# BEEP.net
KiCad netlist of a schematic drawn in Altium Designer
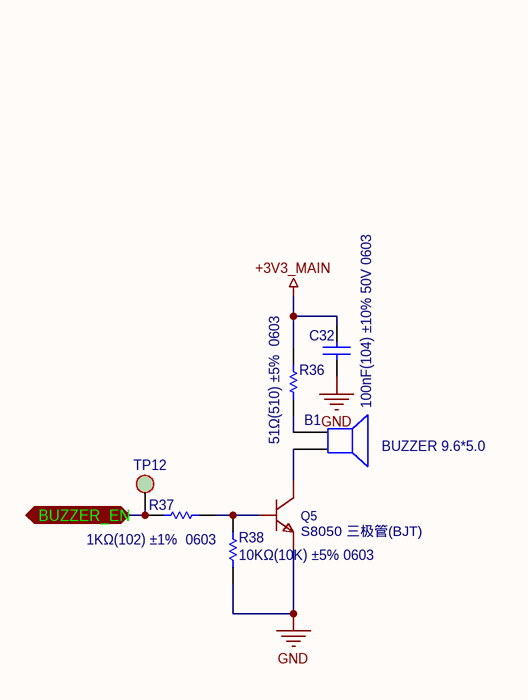
[diagram p0: BEEP.SchDoc]

(export (version "E")
  (design (tool "Eeschema 10.0.6"))
  (components
    (comp (ref "B1")
      (value "BUZZER 9.6*5.0")
      (footprint "BUZZER 9.6×H5.0mm")
      (description "直插蜂鸣器 9.6*5.0")
      (fields (field (name "PUBLISHER") "Altium Limited"))
      (libsource (lib "Miscellaneous Devices") (part "Speaker"))
    )
    (comp (ref "C32")
      (value "100nF(104) ±10% 50V 0603")
      (footprint "C0603")
      (description "0603贴片电容")
      (fields (field (name "PUBLISHER") "Altium Limited"))
      (libsource (lib "Miscellaneous Devices") (part "Cap"))
    )
    (comp (ref "Q5")
      (value "S8050 三极管(BJT)")
      (footprint "SOT233")
      (description "NPN 三极管(BJT)")
      (fields
        (field (name "BOM_SUPPLIER PART") "C908252")
        (field (name "BOM_MANUFACTURER PART") "S8050")
        (field (name "CONTRIBUTOR") "LCSC")
      )
      (libsource (lib "altium-import") (part "root_0_S8050_C908252_"))
    )
    (comp (ref "R36")
      (value "51Ω(510) ±5%  0603")
      (footprint "R0603")
      (description "0603贴片电阻")
      (fields (field (name "PUBLISHER") "Altium Limited"))
      (libsource (lib "Miscellaneous Devices") (part "Res1"))
    )
    (comp (ref "R37")
      (value "1KΩ(102) ±1%  0603")
      (footprint "R0603")
      (description "0603贴片电阻")
      (fields (field (name "PUBLISHER") "Altium Limited"))
      (libsource (lib "Miscellaneous Devices") (part "Res1"))
    )
    (comp (ref "R38")
      (value "10KΩ(10K) ±5% 0603")
      (footprint "R0603")
      (description "0603贴片电阻")
      (fields (field (name "PUBLISHER") "Altium Limited"))
      (libsource (lib "Miscellaneous Devices") (part "Res1"))
    )
    (comp (ref "TP12") (value "NC") (footprint "TP") (description "测试点") (libsource (lib "Tek") (part "TP")))
  )
  (nets
    (net (code "1") (name "+3V3_MAIN") (class "Default")
      (node (ref "C32") (pin "1") (pinfunction "1_1") (pintype "passive"))
      (node (ref "R36") (pin "2") (pinfunction "2_2") (pintype "passive"))
    )
    (net (code "2") (name "/BUZZER_EN") (class "Default")
      (node (ref "R37") (pin "2") (pinfunction "2_2") (pintype "passive"))
      (node (ref "TP12") (pin "1") (pinfunction "0_1") (pintype "passive"))
    )
    (net (code "3") (name "GND") (class "Default")
      (node (ref "C32") (pin "2") (pinfunction "2_2") (pintype "passive"))
      (node (ref "Q5") (pin "2") (pinfunction "E_2") (pintype "passive"))
      (node (ref "R38") (pin "2") (pinfunction "2_2") (pintype "passive"))
    )
    (net (code "4") (name "Net-(B1-Pad1)") (class "Default")
      (node (ref "B1") (pin "1") (pinfunction "1_1") (pintype "passive"))
      (node (ref "R36") (pin "1") (pinfunction "1_1") (pintype "passive"))
    )
    (net (code "5") (name "Net-(Q5-B)") (class "Default")
      (node (ref "Q5") (pin "1") (pinfunction "B_1") (pintype "passive"))
      (node (ref "R37") (pin "1") (pinfunction "1_1") (pintype "passive"))
      (node (ref "R38") (pin "1") (pinfunction "1_1") (pintype "passive"))
    )
    (net (code "6") (name "Net-(Q5-C)") (class "Default")
      (node (ref "B1") (pin "2") (pinfunction "2_2") (pintype "passive"))
      (node (ref "Q5") (pin "3") (pinfunction "C_3") (pintype "passive"))
    )
  )
)
